# pure_midi.net
KiCad netlist of a schematic drawn in EAGLE
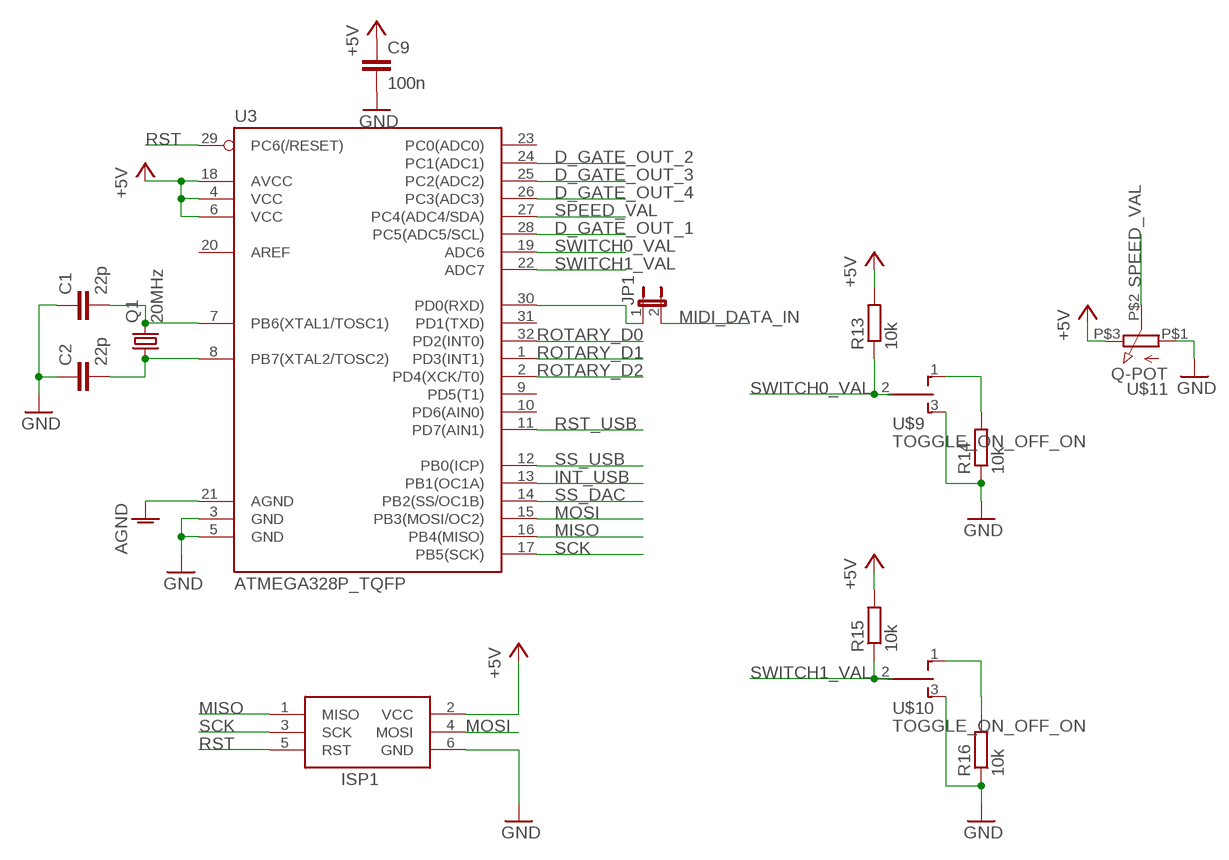
[diagram p0: schematic, sheet 1]
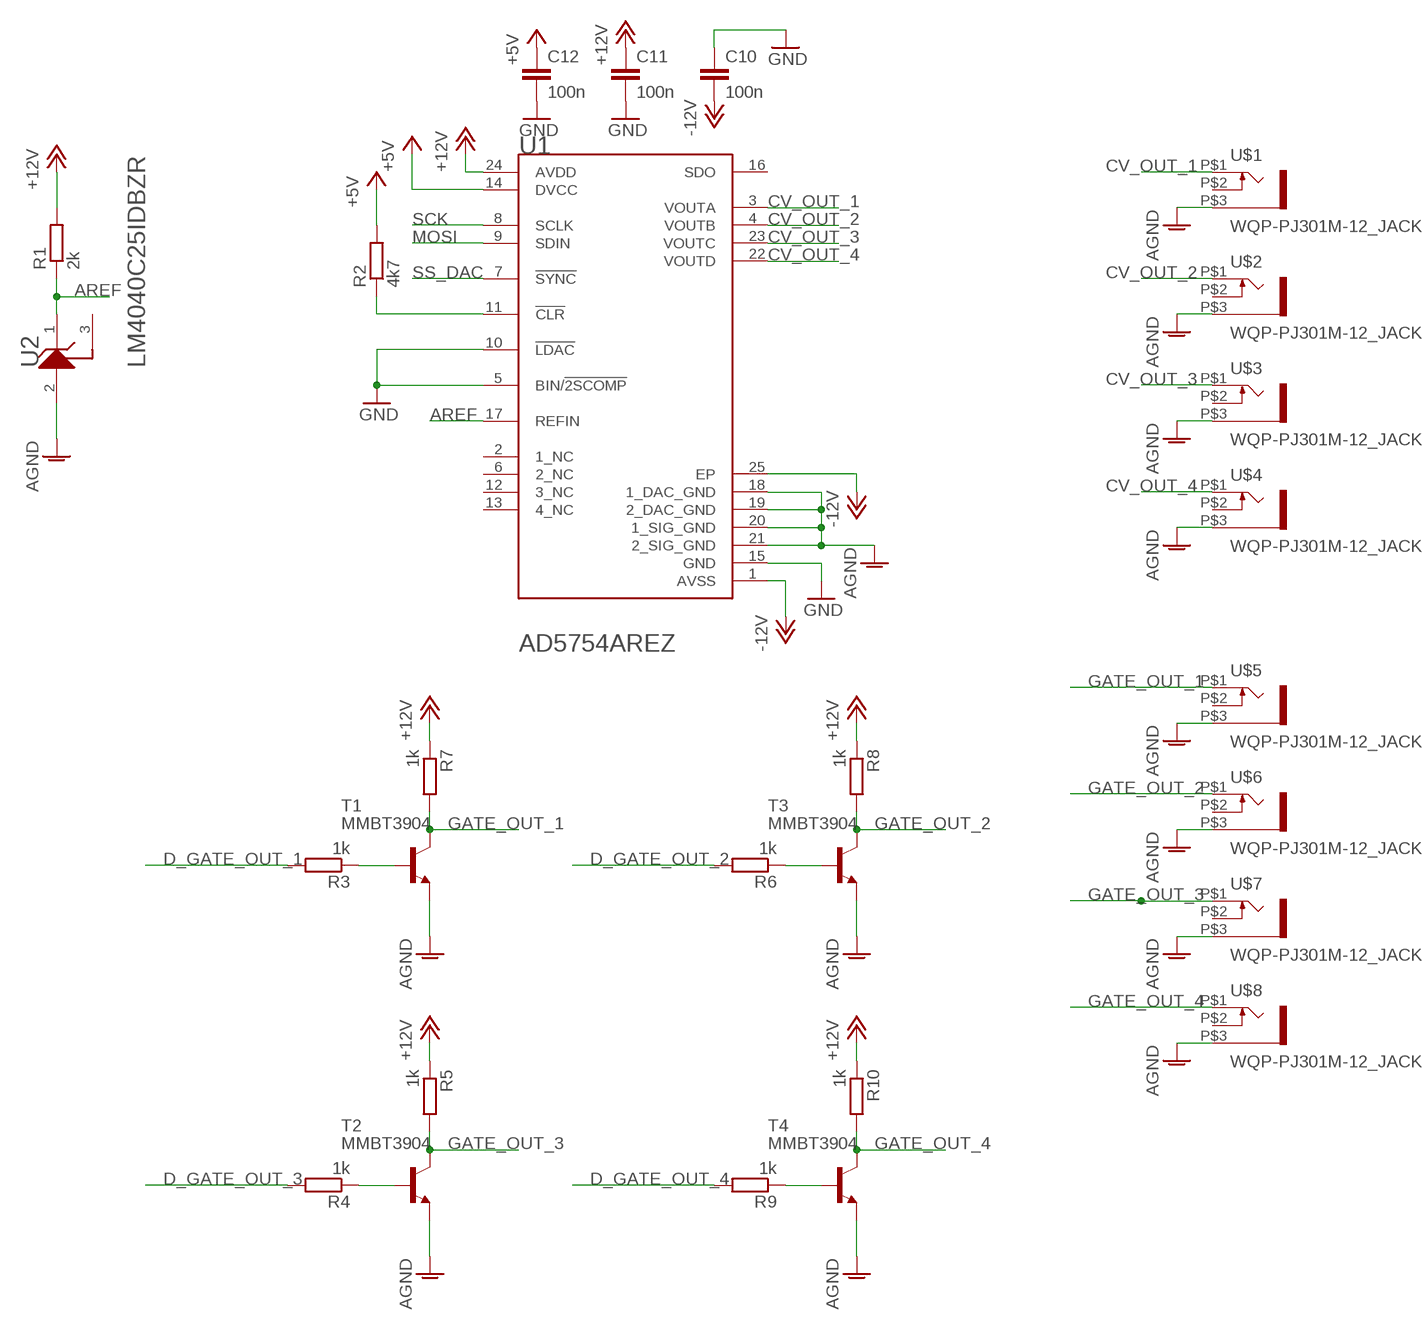
[diagram p1: schematic, sheet 2]
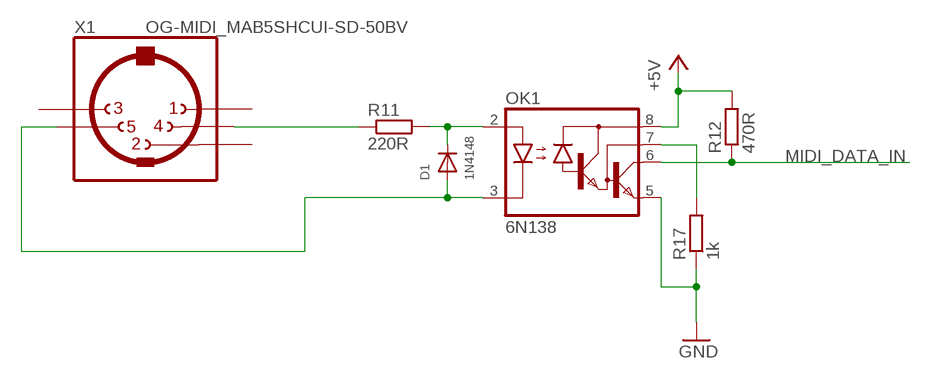
[diagram p2: schematic, sheet 3]
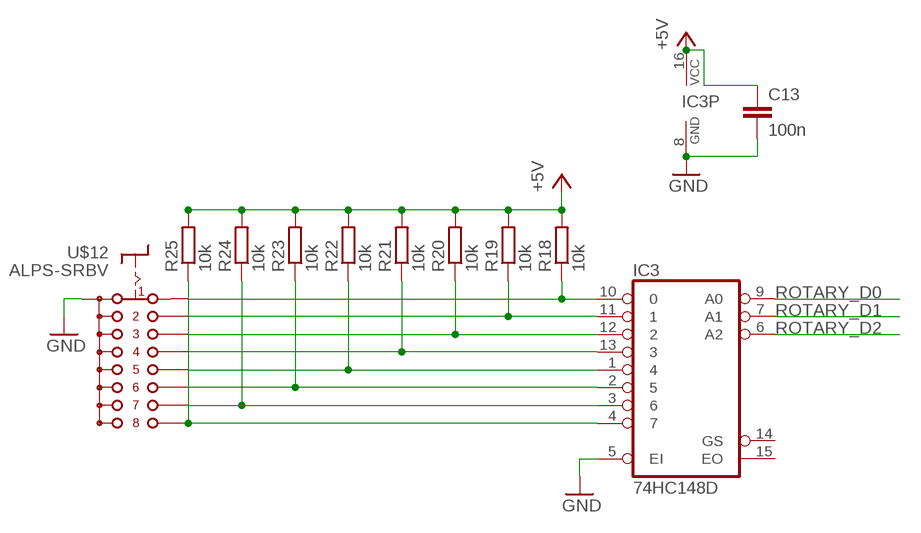
[diagram p3: schematic, sheet 4]
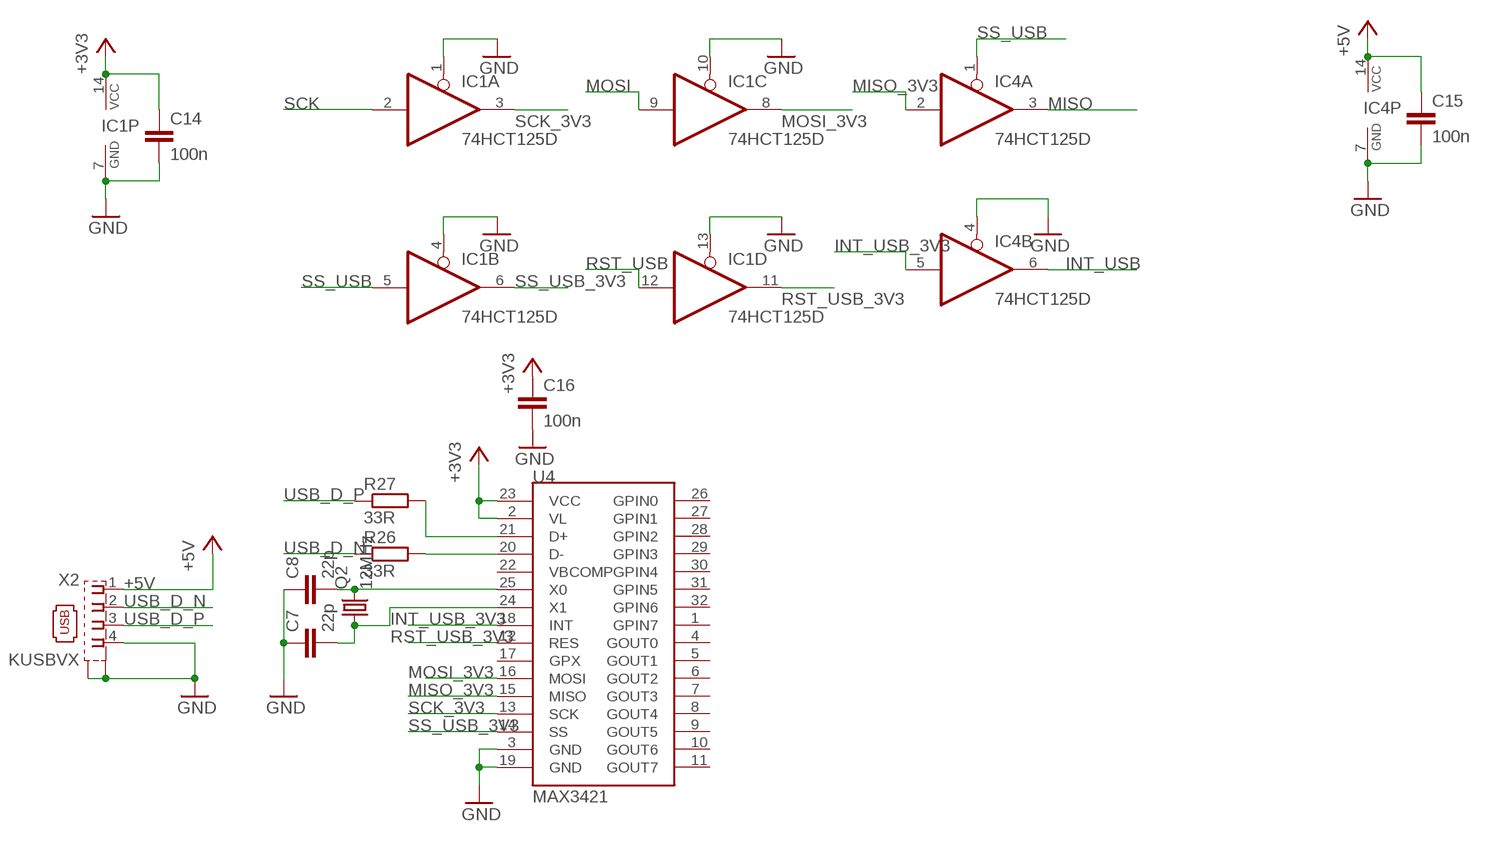
[diagram p4: schematic, sheet 5]
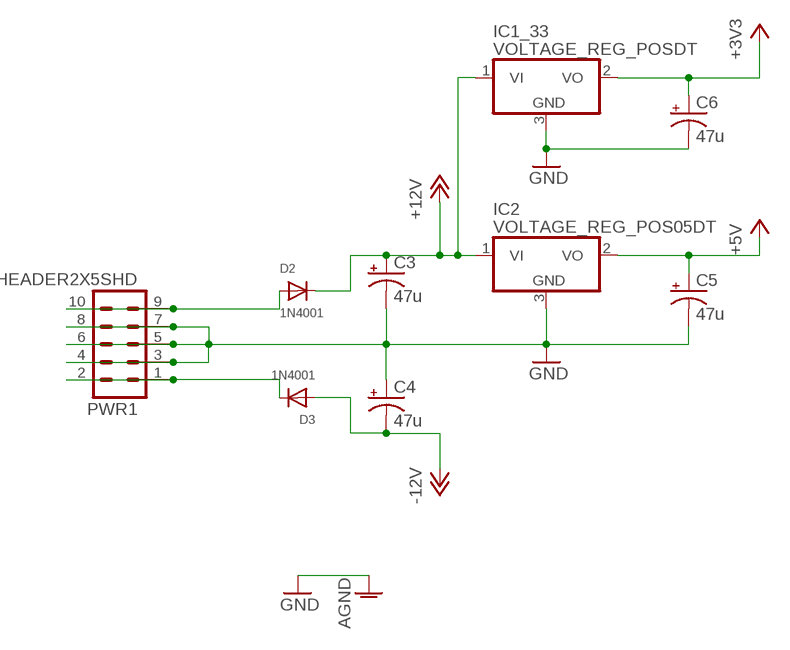
[diagram p5: schematic, sheet 6]

(export (version "E")
  (design (tool "Eeschema 10.0.6"))
  (components
    (comp (ref "C10")
      (value "100n")
      (footprint "eagle-import:C0805")
      (libsource (lib "eagle-import") (part "C-EUC0805"))
    )
    (comp (ref "C11")
      (value "100n")
      (footprint "eagle-import:C0805")
      (libsource (lib "eagle-import") (part "C-EUC0805"))
    )
    (comp (ref "C12")
      (value "100n")
      (footprint "eagle-import:C0805")
      (libsource (lib "eagle-import") (part "C-EUC0805"))
    )
    (comp (ref "R1")
      (value "2k")
      (footprint "eagle-import:R0805")
      (libsource (lib "eagle-import") (part "R-EU_R0805"))
    )
    (comp (ref "R2")
      (value "4k7")
      (footprint "eagle-import:R0805")
      (libsource (lib "eagle-import") (part "R-EU_R0805"))
    )
    (comp (ref "R3")
      (value "1k")
      (footprint "eagle-import:R0805")
      (libsource (lib "eagle-import") (part "R-EU_R0805"))
    )
    (comp (ref "R4")
      (value "1k")
      (footprint "eagle-import:R0805")
      (libsource (lib "eagle-import") (part "R-EU_R0805"))
    )
    (comp (ref "R5")
      (value "1k")
      (footprint "eagle-import:R0805")
      (libsource (lib "eagle-import") (part "R-EU_R0805"))
    )
    (comp (ref "R6")
      (value "1k")
      (footprint "eagle-import:R0805")
      (libsource (lib "eagle-import") (part "R-EU_R0805"))
    )
    (comp (ref "R7")
      (value "1k")
      (footprint "eagle-import:R0805")
      (libsource (lib "eagle-import") (part "R-EU_R0805"))
    )
    (comp (ref "R8")
      (value "1k")
      (footprint "eagle-import:R0805")
      (libsource (lib "eagle-import") (part "R-EU_R0805"))
    )
    (comp (ref "R9")
      (value "1k")
      (footprint "eagle-import:R0805")
      (libsource (lib "eagle-import") (part "R-EU_R0805"))
    )
    (comp (ref "R10")
      (value "1k")
      (footprint "eagle-import:R0805")
      (libsource (lib "eagle-import") (part "R-EU_R0805"))
    )
    (comp (ref "T1")
      (value "MMBT3904")
      (footprint "eagle-import:SOT23-EBC")
      (libsource (lib "eagle-import") (part "-NPN-SOT23-EBC"))
    )
    (comp (ref "T2")
      (value "MMBT3904")
      (footprint "eagle-import:SOT23-EBC")
      (libsource (lib "eagle-import") (part "-NPN-SOT23-EBC"))
    )
    (comp (ref "T3")
      (value "MMBT3904")
      (footprint "eagle-import:SOT23-EBC")
      (libsource (lib "eagle-import") (part "-NPN-SOT23-EBC"))
    )
    (comp (ref "T4")
      (value "MMBT3904")
      (footprint "eagle-import:SOT23-EBC")
      (libsource (lib "eagle-import") (part "-NPN-SOT23-EBC"))
    )
    (comp (ref "U$1")
      (value "WQP-PJ301M-12_JACK")
      (footprint "eagle-import:WQP-PJ301M-12_JACK")
      (libsource (lib "eagle-import") (part "WQP-PJ301M-12_JACK"))
    )
    (comp (ref "U$2")
      (value "WQP-PJ301M-12_JACK")
      (footprint "eagle-import:WQP-PJ301M-12_JACK")
      (libsource (lib "eagle-import") (part "WQP-PJ301M-12_JACK"))
    )
    (comp (ref "U$3")
      (value "WQP-PJ301M-12_JACK")
      (footprint "eagle-import:WQP-PJ301M-12_JACK")
      (libsource (lib "eagle-import") (part "WQP-PJ301M-12_JACK"))
    )
    (comp (ref "U$4")
      (value "WQP-PJ301M-12_JACK")
      (footprint "eagle-import:WQP-PJ301M-12_JACK")
      (libsource (lib "eagle-import") (part "WQP-PJ301M-12_JACK"))
    )
    (comp (ref "U$5")
      (value "WQP-PJ301M-12_JACK")
      (footprint "eagle-import:WQP-PJ301M-12_JACK")
      (libsource (lib "eagle-import") (part "WQP-PJ301M-12_JACK"))
    )
    (comp (ref "U$6")
      (value "WQP-PJ301M-12_JACK")
      (footprint "eagle-import:WQP-PJ301M-12_JACK")
      (libsource (lib "eagle-import") (part "WQP-PJ301M-12_JACK"))
    )
    (comp (ref "U$7")
      (value "WQP-PJ301M-12_JACK")
      (footprint "eagle-import:WQP-PJ301M-12_JACK")
      (libsource (lib "eagle-import") (part "WQP-PJ301M-12_JACK"))
    )
    (comp (ref "U$8")
      (value "WQP-PJ301M-12_JACK")
      (footprint "eagle-import:WQP-PJ301M-12_JACK")
      (libsource (lib "eagle-import") (part "WQP-PJ301M-12_JACK"))
    )
    (comp (ref "U1")
      (value "ANALOG_DEVICES_INC_AD5754AREZANALOG_DEVICES_INC_AD5754AREZ_0_0")
      (footprint "eagle-import:ANALOG_DEVICES_INC_AD5754AREZ_0")
      (fields
        (field (name "DIGIKEY_PART_NUMBER") "AD5754AREZ-ND")
        (field (name "MF") "Analog Devices Inc")
        (field (name "MOUSER_PART_NUMBER") "584-AD5754AREZ")
      )
      (libsource (lib "eagle-import") (part "ANALOG_DEVICES_INC_AD5754AREZANALOG_DEVICES_INC_AD5754AREZ_0_0"))
    )
    (comp (ref "U2")
      (value "TEXAS_INSTRUMENTS_LM4040C25IDBZRTEXAS_INSTRUMENTS_LM4040C25IDBZR_0_1")
      (footprint "eagle-import:TEXAS_INSTRUMENTS_LM4040C25IDBZR_1")
      (fields (field (name "MF") "Texas Instruments") (field (name "MPN") "LM4040C25IDBZR"))
      (libsource (lib "eagle-import") (part "TEXAS_INSTRUMENTS_LM4040C25IDBZRTEXAS_INSTRUMENTS_LM4040C25IDBZR_0_1"))
    )
    (comp (ref "C3")
      (value "47u")
      (footprint "eagle-import:153CLV-0505")
      (libsource (lib "eagle-import") (part "CAPACITOR_POL-US153CLV-0505"))
    )
    (comp (ref "C4")
      (value "47u")
      (footprint "eagle-import:153CLV-0505")
      (libsource (lib "eagle-import") (part "CAPACITOR_POL-US153CLV-0505"))
    )
    (comp (ref "C5")
      (value "47u")
      (footprint "eagle-import:153CLV-0505")
      (libsource (lib "eagle-import") (part "CAPACITOR_POL-US153CLV-0505"))
    )
    (comp (ref "C6")
      (value "47u")
      (footprint "eagle-import:153CLV-0505")
      (libsource (lib "eagle-import") (part "CAPACITOR_POL-US153CLV-0505"))
    )
    (comp (ref "D2")
      (value "1N4001")
      (footprint "eagle-import:SMADIODE")
      (libsource (lib "eagle-import") (part "DIODESMA"))
    )
    (comp (ref "D3")
      (value "1N4001")
      (footprint "eagle-import:SMADIODE")
      (libsource (lib "eagle-import") (part "DIODESMA"))
    )
    (comp (ref "IC1_33")
      (value "VOLTAGE_REG_POSDT")
      (footprint "eagle-import:TO252")
      (libsource (lib "eagle-import") (part "VOLTAGE_REG_POSDT"))
    )
    (comp (ref "IC2")
      (value "VOLTAGE_REG_POS05DT")
      (footprint "eagle-import:TO252")
      (libsource (lib "eagle-import") (part "VOLTAGE_REG_POSDT05"))
    )
    (comp (ref "PWR1")
      (value "HEADER2X5SHD")
      (footprint "eagle-import:2X5-SHROUDED")
      (libsource (lib "eagle-import") (part "HEADER2X5SHD"))
    )
    (comp (ref "C7")
      (value "22p")
      (footprint "eagle-import:C0805")
      (libsource (lib "eagle-import") (part "C-EUC0805"))
    )
    (comp (ref "C8")
      (value "22p")
      (footprint "eagle-import:C0805")
      (libsource (lib "eagle-import") (part "C-EUC0805"))
    )
    (comp (ref "C14")
      (value "100n")
      (footprint "eagle-import:C0805")
      (libsource (lib "eagle-import") (part "C-EUC0805"))
    )
    (comp (ref "C15")
      (value "100n")
      (footprint "eagle-import:C0805")
      (libsource (lib "eagle-import") (part "C-EUC0805"))
    )
    (comp (ref "C16")
      (value "100n")
      (footprint "eagle-import:C0805")
      (libsource (lib "eagle-import") (part "C-EUC0805"))
    )
    (comp (ref "IC1")
      (value "74HCT125D")
      (footprint "eagle-import:SO14")
      (libsource (lib "eagle-import") (part "74125DHCT"))
    )
    (comp (ref "IC4")
      (value "74HCT125D")
      (footprint "eagle-import:SO14")
      (libsource (lib "eagle-import") (part "74125DHCT"))
    )
    (comp (ref "Q2")
      (value "12MHz")
      (footprint "eagle-import:HC49UP")
      (libsource (lib "eagle-import") (part "CRYSTALHC49UP"))
    )
    (comp (ref "R26")
      (value "33R")
      (footprint "eagle-import:R0805")
      (libsource (lib "eagle-import") (part "R-EU_R0805"))
    )
    (comp (ref "R27")
      (value "33R")
      (footprint "eagle-import:R0805")
      (libsource (lib "eagle-import") (part "R-EU_R0805"))
    )
    (comp (ref "U4")
      (value "MAX3421")
      (footprint "eagle-import:TQFP32-5MM")
      (libsource (lib "eagle-import") (part "MAX3421ESMD"))
    )
    (comp (ref "X2")
      (value "KUSBVX")
      (footprint "eagle-import:KUSBVX")
      (libsource (lib "eagle-import") (part "KUSBVX"))
    )
    (comp (ref "C1")
      (value "22p")
      (footprint "eagle-import:C0805")
      (libsource (lib "eagle-import") (part "C-EUC0805"))
    )
    (comp (ref "C2")
      (value "22p")
      (footprint "eagle-import:C0805")
      (libsource (lib "eagle-import") (part "C-EUC0805"))
    )
    (comp (ref "C9")
      (value "100n")
      (footprint "eagle-import:C0805")
      (libsource (lib "eagle-import") (part "C-EUC0805"))
    )
    (comp (ref "ISP1")
      (value "AVRISP-6")
      (footprint "eagle-import:AVRISP")
      (libsource (lib "eagle-import") (part "AVRISP-6"))
    )
    (comp (ref "JP1")
      (value "JP1E")
      (footprint "eagle-import:JP1")
      (libsource (lib "eagle-import") (part "JP1E"))
    )
    (comp (ref "Q1")
      (value "20MHz")
      (footprint "eagle-import:HC49UP")
      (libsource (lib "eagle-import") (part "CRYSTALHC49UP"))
    )
    (comp (ref "R13")
      (value "10k")
      (footprint "eagle-import:R0805")
      (libsource (lib "eagle-import") (part "resistor_348_R-EU_R0805"))
    )
    (comp (ref "R14")
      (value "10k")
      (footprint "eagle-import:R0805")
      (libsource (lib "eagle-import") (part "resistor_348_R-EU_R0805"))
    )
    (comp (ref "R15")
      (value "10k")
      (footprint "eagle-import:R0805")
      (libsource (lib "eagle-import") (part "resistor_348_R-EU_R0805"))
    )
    (comp (ref "R16")
      (value "10k")
      (footprint "eagle-import:R0805")
      (libsource (lib "eagle-import") (part "resistor_348_R-EU_R0805"))
    )
    (comp (ref "U$9")
      (value "TOGGLE_ON_OFF_ON")
      (footprint "eagle-import:TOGGLE_ON_OFF_ON")
      (libsource (lib "eagle-import") (part "TOGGLE_ON_OFF_ON"))
    )
    (comp (ref "U$10")
      (value "TOGGLE_ON_OFF_ON")
      (footprint "eagle-import:TOGGLE_ON_OFF_ON")
      (libsource (lib "eagle-import") (part "TOGGLE_ON_OFF_ON"))
    )
    (comp (ref "U$11")
      (value "Q-POT")
      (footprint "eagle-import:Q-POT")
      (libsource (lib "eagle-import") (part "Q-POT"))
    )
    (comp (ref "U3")
      (value "ATMEGA328P_TQFP")
      (footprint "eagle-import:TQFP32-08")
      (libsource (lib "eagle-import") (part "ATMEGA328P_TQFP"))
    )
    (comp (ref "C13")
      (value "100n")
      (footprint "eagle-import:C0805")
      (libsource (lib "eagle-import") (part "C-EUC0805"))
    )
    (comp (ref "IC3")
      (value "74HC148D")
      (footprint "eagle-import:SO16")
      (libsource (lib "eagle-import") (part "74148DHC"))
    )
    (comp (ref "R18")
      (value "10k")
      (footprint "eagle-import:R0805")
      (libsource (lib "eagle-import") (part "R-EU_R0805"))
    )
    (comp (ref "R19")
      (value "10k")
      (footprint "eagle-import:R0805")
      (libsource (lib "eagle-import") (part "R-EU_R0805"))
    )
    (comp (ref "R20")
      (value "10k")
      (footprint "eagle-import:R0805")
      (libsource (lib "eagle-import") (part "R-EU_R0805"))
    )
    (comp (ref "R21")
      (value "10k")
      (footprint "eagle-import:R0805")
      (libsource (lib "eagle-import") (part "R-EU_R0805"))
    )
    (comp (ref "R22")
      (value "10k")
      (footprint "eagle-import:R0805")
      (libsource (lib "eagle-import") (part "R-EU_R0805"))
    )
    (comp (ref "R23")
      (value "10k")
      (footprint "eagle-import:R0805")
      (libsource (lib "eagle-import") (part "R-EU_R0805"))
    )
    (comp (ref "R24")
      (value "10k")
      (footprint "eagle-import:R0805")
      (libsource (lib "eagle-import") (part "R-EU_R0805"))
    )
    (comp (ref "R25")
      (value "10k")
      (footprint "eagle-import:R0805")
      (libsource (lib "eagle-import") (part "R-EU_R0805"))
    )
    (comp (ref "U$12")
      (value "ALPS-SRBV")
      (footprint "eagle-import:ALPS-SRBV")
      (libsource (lib "eagle-import") (part "ALPS-SRBV"))
    )
    (comp (ref "D1")
      (value "1N4148")
      (footprint "eagle-import:SOD-323F")
      (libsource (lib "eagle-import") (part "adafruit_420_DIODESOD-323F"))
    )
    (comp (ref "OK1")
      (value "6N138")
      (footprint "eagle-import:DIL08")
      (fields (field (name "MF") "VISHAY/TELEFUNKEN"))
      (libsource (lib "eagle-import") (part "6N138"))
    )
    (comp (ref "R11")
      (value "220R")
      (footprint "eagle-import:R0805")
      (libsource (lib "eagle-import") (part "resistor_348_R-EU_R0805"))
    )
    (comp (ref "R12")
      (value "470R")
      (footprint "eagle-import:R0805")
      (libsource (lib "eagle-import") (part "resistor_348_R-EU_R0805"))
    )
    (comp (ref "R17")
      (value "1k")
      (footprint "eagle-import:R0805")
      (libsource (lib "eagle-import") (part "resistor_348_R-EU_R0805"))
    )
    (comp (ref "X1")
      (value "OG-MIDI_MAB5SHCUI-SD-50BV")
      (footprint "eagle-import:OG-MIDI_SD-50BV")
      (libsource (lib "eagle-import") (part "OG-MIDI_MAB5SHCUI-SD-50BV"))
    )
  )
  (nets
    (net (code "1") (name "+3V3") (class "Default")
      (node (ref "C14") (pin "1") (pinfunction "1_1") (pintype "passive"))
      (node (ref "C16") (pin "1") (pinfunction "1_1") (pintype "passive"))
      (node (ref "C6") (pin "+") (pinfunction "+_+") (pintype "passive"))
      (node (ref "IC1") (pin "14") (pinfunction "VCC_14") (pintype "power_in"))
      (node (ref "IC1_33") (pin "2") (pinfunction "VO_2") (pintype "passive"))
      (node (ref "U4") (pin "2") (pinfunction "VL_2") (pintype "bidirectional"))
      (node (ref "U4") (pin "23") (pinfunction "VCC_23") (pintype "bidirectional"))
    )
    (net (code "2") (name "+5V") (class "Default")
      (node (ref "C12") (pin "1") (pinfunction "1_1") (pintype "passive"))
      (node (ref "C13") (pin "1") (pinfunction "1_1") (pintype "passive"))
      (node (ref "C15") (pin "1") (pinfunction "1_1") (pintype "passive"))
      (node (ref "C5") (pin "+") (pinfunction "+_+") (pintype "passive"))
      (node (ref "C9") (pin "1") (pinfunction "1_1") (pintype "passive"))
      (node (ref "IC2") (pin "2") (pinfunction "VO_2") (pintype "passive"))
      (node (ref "IC3") (pin "16") (pinfunction "VCC_16") (pintype "power_in"))
      (node (ref "IC4") (pin "14") (pinfunction "VCC_14") (pintype "power_in"))
      (node (ref "ISP1") (pin "2") (pinfunction "VCC_2") (pintype "power_in"))
      (node (ref "OK1") (pin "8") (pinfunction "VCC_8") (pintype "passive"))
      (node (ref "R12") (pin "2") (pinfunction "2_2") (pintype "passive"))
      (node (ref "R13") (pin "2") (pinfunction "2_2") (pintype "passive"))
      (node (ref "R15") (pin "2") (pinfunction "2_2") (pintype "passive"))
      (node (ref "R18") (pin "2") (pinfunction "2_2") (pintype "passive"))
      (node (ref "R19") (pin "2") (pinfunction "2_2") (pintype "passive"))
      (node (ref "R2") (pin "2") (pinfunction "2_2") (pintype "passive"))
      (node (ref "R20") (pin "2") (pinfunction "2_2") (pintype "passive"))
      (node (ref "R21") (pin "2") (pinfunction "2_2") (pintype "passive"))
      (node (ref "R22") (pin "2") (pinfunction "2_2") (pintype "passive"))
      (node (ref "R23") (pin "2") (pinfunction "2_2") (pintype "passive"))
      (node (ref "R24") (pin "2") (pinfunction "2_2") (pintype "passive"))
      (node (ref "R25") (pin "2") (pinfunction "2_2") (pintype "passive"))
      (node (ref "U$11") (pin "P$3") (pinfunction "3_P$3") (pintype "passive"))
      (node (ref "U1") (pin "14") (pinfunction "DVCC_14") (pintype "power_in"))
      (node (ref "U3") (pin "18") (pinfunction "AVCC_18") (pintype "bidirectional"))
      (node (ref "U3") (pin "4") (pinfunction "VCC_4") (pintype "bidirectional"))
      (node (ref "U3") (pin "6") (pinfunction "VCC_6") (pintype "bidirectional"))
      (node (ref "X2") (pin "1") (pinfunction "1_1") (pintype "passive"))
    )
    (net (code "3") (name "+12V") (class "Default")
      (node (ref "C11") (pin "1") (pinfunction "1_1") (pintype "passive"))
      (node (ref "C3") (pin "+") (pinfunction "+_+") (pintype "passive"))
      (node (ref "D2") (pin "C") (pinfunction "C_C") (pintype "passive"))
      (node (ref "IC1_33") (pin "1") (pinfunction "VI_1") (pintype "input"))
      (node (ref "IC2") (pin "1") (pinfunction "VI_1") (pintype "input"))
      (node (ref "R1") (pin "2") (pinfunction "2_2") (pintype "passive"))
      (node (ref "R10") (pin "1") (pinfunction "1_1") (pintype "passive"))
      (node (ref "R5") (pin "1") (pinfunction "1_1") (pintype "passive"))
      (node (ref "R7") (pin "1") (pinfunction "1_1") (pintype "passive"))
      (node (ref "R8") (pin "1") (pinfunction "1_1") (pintype "passive"))
      (node (ref "U1") (pin "24") (pinfunction "AVDD_24") (pintype "power_in"))
    )
    (net (code "4") (name "-12V") (class "Default")
      (node (ref "C10") (pin "2") (pinfunction "2_2") (pintype "passive"))
      (node (ref "C4") (pin "-") (pinfunction "-_-") (pintype "passive"))
      (node (ref "D3") (pin "A") (pinfunction "A_A") (pintype "passive"))
      (node (ref "U1") (pin "1") (pinfunction "AVSS_1") (pintype "power_in"))
      (node (ref "U1") (pin "25") (pinfunction "EP_25") (pintype "power_in"))
    )
    (net (code "5") (name "AGND") (class "Default")
      (node (ref "C1") (pin "1") (pinfunction "1_1") (pintype "passive"))
      (node (ref "C10") (pin "1") (pinfunction "1_1") (pintype "passive"))
      (node (ref "C11") (pin "2") (pinfunction "2_2") (pintype "passive"))
      (node (ref "C12") (pin "2") (pinfunction "2_2") (pintype "passive"))
      (node (ref "C13") (pin "2") (pinfunction "2_2") (pintype "passive"))
      (node (ref "C14") (pin "2") (pinfunction "2_2") (pintype "passive"))
      (node (ref "C15") (pin "2") (pinfunction "2_2") (pintype "passive"))
      (node (ref "C16") (pin "2") (pinfunction "2_2") (pintype "passive"))
      (node (ref "C2") (pin "1") (pinfunction "1_1") (pintype "passive"))
      (node (ref "C3") (pin "-") (pinfunction "-_-") (pintype "passive"))
      (node (ref "C4") (pin "+") (pinfunction "+_+") (pintype "passive"))
      (node (ref "C5") (pin "-") (pinfunction "-_-") (pintype "passive"))
      (node (ref "C6") (pin "-") (pinfunction "-_-") (pintype "passive"))
      (node (ref "C7") (pin "1") (pinfunction "1_1") (pintype "passive"))
      (node (ref "C8") (pin "1") (pinfunction "1_1") (pintype "passive"))
      (node (ref "C9") (pin "2") (pinfunction "2_2") (pintype "passive"))
      (node (ref "IC1") (pin "1") (pinfunction "OE_1") (pintype "input"))
      (node (ref "IC1") (pin "10") (pinfunction "OE_10") (pintype "input"))
      (node (ref "IC1") (pin "13") (pinfunction "OE_13") (pintype "input"))
      (node (ref "IC1") (pin "4") (pinfunction "OE_4") (pintype "input"))
      (node (ref "IC1") (pin "7") (pinfunction "GND_7") (pintype "power_in"))
      (node (ref "IC1_33") (pin "3") (pinfunction "GND_3") (pintype "passive"))
      (node (ref "IC2") (pin "3") (pinfunction "GND_3") (pintype "passive"))
      (node (ref "IC3") (pin "5") (pinfunction "EI_5") (pintype "input"))
      (node (ref "IC3") (pin "8") (pinfunction "GND_8") (pintype "power_in"))
      (node (ref "IC4") (pin "4") (pinfunction "OE_4") (pintype "input"))
      (node (ref "IC4") (pin "7") (pinfunction "GND_7") (pintype "power_in"))
      (node (ref "ISP1") (pin "6") (pinfunction "GND_6") (pintype "power_in"))
      (node (ref "OK1") (pin "5") (pinfunction "GND_5") (pintype "passive"))
      (node (ref "PWR1") (pin "3") (pinfunction "3_3") (pintype "passive"))
      (node (ref "PWR1") (pin "4") (pinfunction "4_4") (pintype "passive"))
      (node (ref "PWR1") (pin "5") (pinfunction "5_5") (pintype "passive"))
      (node (ref "PWR1") (pin "6") (pinfunction "6_6") (pintype "passive"))
      (node (ref "PWR1") (pin "7") (pinfunction "7_7") (pintype "passive"))
      (node (ref "PWR1") (pin "8") (pinfunction "8_8") (pintype "passive"))
      (node (ref "R14") (pin "1") (pinfunction "1_1") (pintype "passive"))
      (node (ref "R16") (pin "1") (pinfunction "1_1") (pintype "passive"))
      (node (ref "R17") (pin "1") (pinfunction "1_1") (pintype "passive"))
      (node (ref "T1") (pin "E") (pinfunction "E_E") (pintype "passive"))
      (node (ref "T2") (pin "E") (pinfunction "E_E") (pintype "passive"))
      (node (ref "T3") (pin "E") (pinfunction "E_E") (pintype "passive"))
      (node (ref "T4") (pin "E") (pinfunction "E_E") (pintype "passive"))
      (node (ref "U$1") (pin "P$3") (pinfunction "1_P$3") (pintype "passive"))
      (node (ref "U$10") (pin "3") (pinfunction "S_3") (pintype "passive"))
      (node (ref "U$11") (pin "P$1") (pinfunction "1_P$1") (pintype "passive"))
      (node (ref "U$12") (pin "COM") (pinfunction "A_COM") (pintype "passive"))
      (node (ref "U$12") (pin "COM2") (pinfunction "A_COM2") (pintype "passive"))
      (node (ref "U$2") (pin "P$3") (pinfunction "1_P$3") (pintype "passive"))
      (node (ref "U$3") (pin "P$3") (pinfunction "1_P$3") (pintype "passive"))
      (node (ref "U$4") (pin "P$3") (pinfunction "1_P$3") (pintype "passive"))
      (node (ref "U$5") (pin "P$3") (pinfunction "1_P$3") (pintype "passive"))
      (node (ref "U$6") (pin "P$3") (pinfunction "1_P$3") (pintype "passive"))
      (node (ref "U$7") (pin "P$3") (pinfunction "1_P$3") (pintype "passive"))
      (node (ref "U$8") (pin "P$3") (pinfunction "1_P$3") (pintype "passive"))
      (node (ref "U$9") (pin "3") (pinfunction "S_3") (pintype "passive"))
      (node (ref "U1") (pin "10") (pinfunction "~{LDAC}_10") (pintype "input"))
      (node (ref "U1") (pin "15") (pinfunction "GND_15") (pintype "power_in"))
      (node (ref "U1") (pin "18") (pinfunction "1_DAC_GND_18") (pintype "power_in"))
      (node (ref "U1") (pin "19") (pinfunction "2_DAC_GND_19") (pintype "power_in"))
      (node (ref "U1") (pin "20") (pinfunction "1_SIG_GND_20") (pintype "power_in"))
      (node (ref "U1") (pin "21") (pinfunction "2_SIG_GND_21") (pintype "power_in"))
      (node (ref "U1") (pin "5") (pinfunction "BIN/~{2SCOMP}_5") (pintype "input"))
      (node (ref "U2") (pin "2") (pinfunction "ANODE_2") (pintype "passive"))
      (node (ref "U3") (pin "21") (pinfunction "AGND_21") (pintype "bidirectional"))
      (node (ref "U3") (pin "3") (pinfunction "GND_3") (pintype "bidirectional"))
      (node (ref "U3") (pin "5") (pinfunction "GND_5") (pintype "bidirectional"))
      (node (ref "U4") (pin "19") (pinfunction "GND_19") (pintype "bidirectional"))
      (node (ref "U4") (pin "3") (pinfunction "GND_3") (pintype "bidirectional"))
      (node (ref "X2") (pin "4") (pinfunction "4_4") (pintype "passive"))
      (node (ref "X2") (pin "M1") (pinfunction "S1_M1") (pintype "passive"))
      (node (ref "X2") (pin "M2") (pinfunction "S2_M2") (pintype "passive"))
    )
    (net (code "6") (name "AREF") (class "Default")
      (node (ref "R1") (pin "1") (pinfunction "1_1") (pintype "passive"))
      (node (ref "U1") (pin "17") (pinfunction "REFIN_17") (pintype "input"))
      (node (ref "U2") (pin "1") (pinfunction "CATHODE_1") (pintype "passive"))
    )
    (net (code "7") (name "CV_OUT_1") (class "Default")
      (node (ref "U$1") (pin "P$1") (pinfunction "2_P$1") (pintype "passive"))
      (node (ref "U1") (pin "3") (pinfunction "VOUTA_3") (pintype "output"))
    )
    (net (code "8") (name "CV_OUT_2") (class "Default")
      (node (ref "U$2") (pin "P$1") (pinfunction "2_P$1") (pintype "passive"))
      (node (ref "U1") (pin "4") (pinfunction "VOUTB_4") (pintype "output"))
    )
    (net (code "9") (name "CV_OUT_3") (class "Default")
      (node (ref "U$3") (pin "P$1") (pinfunction "2_P$1") (pintype "passive"))
      (node (ref "U1") (pin "23") (pinfunction "VOUTC_23") (pintype "output"))
    )
    (net (code "10") (name "CV_OUT_4") (class "Default")
      (node (ref "U$4") (pin "P$1") (pinfunction "2_P$1") (pintype "passive"))
      (node (ref "U1") (pin "22") (pinfunction "VOUTD_22") (pintype "output"))
    )
    (net (code "11") (name "D_GATE_OUT_1") (class "Default")
      (node (ref "R3") (pin "2") (pinfunction "2_2") (pintype "passive"))
      (node (ref "U3") (pin "28") (pinfunction "PC5(ADC5/SCL)_28") (pintype "bidirectional"))
    )
    (net (code "12") (name "D_GATE_OUT_2") (class "Default")
      (node (ref "R6") (pin "2") (pinfunction "2_2") (pintype "passive"))
      (node (ref "U3") (pin "24") (pinfunction "PC1(ADC1)_24") (pintype "bidirectional"))
    )
    (net (code "13") (name "D_GATE_OUT_3") (class "Default")
      (node (ref "R4") (pin "2") (pinfunction "2_2") (pintype "passive"))
      (node (ref "U3") (pin "25") (pinfunction "PC2(ADC2)_25") (pintype "bidirectional"))
    )
    (net (code "14") (name "D_GATE_OUT_4") (class "Default")
      (node (ref "R9") (pin "2") (pinfunction "2_2") (pintype "passive"))
      (node (ref "U3") (pin "26") (pinfunction "PC3(ADC3)_26") (pintype "bidirectional"))
    )
    (net (code "15") (name "GATE_OUT_1") (class "Default")
      (node (ref "R7") (pin "2") (pinfunction "2_2") (pintype "passive"))
      (node (ref "T1") (pin "C") (pinfunction "C_C") (pintype "passive"))
      (node (ref "U$5") (pin "P$1") (pinfunction "2_P$1") (pintype "passive"))
    )
    (net (code "16") (name "GATE_OUT_2") (class "Default")
      (node (ref "R8") (pin "2") (pinfunction "2_2") (pintype "passive"))
      (node (ref "T3") (pin "C") (pinfunction "C_C") (pintype "passive"))
      (node (ref "U$6") (pin "P$1") (pinfunction "2_P$1") (pintype "passive"))
    )
    (net (code "17") (name "GATE_OUT_3") (class "Default")
      (node (ref "R5") (pin "2") (pinfunction "2_2") (pintype "passive"))
      (node (ref "T2") (pin "C") (pinfunction "C_C") (pintype "passive"))
      (node (ref "U$7") (pin "P$1") (pinfunction "2_P$1") (pintype "passive"))
    )
    (net (code "18") (name "GATE_OUT_4") (class "Default")
      (node (ref "R10") (pin "2") (pinfunction "2_2") (pintype "passive"))
      (node (ref "T4") (pin "C") (pinfunction "C_C") (pintype "passive"))
      (node (ref "U$8") (pin "P$1") (pinfunction "2_P$1") (pintype "passive"))
    )
    (net (code "19") (name "INT_USB") (class "Default")
      (node (ref "IC4") (pin "6") (pinfunction "O_6") (pintype "tri_state"))
      (node (ref "U3") (pin "13") (pinfunction "PB1(OC1A)_13") (pintype "bidirectional"))
    )
    (net (code "20") (name "INT_USB_3V3") (class "Default")
      (node (ref "IC4") (pin "5") (pinfunction "I_5") (pintype "input"))
      (node (ref "U4") (pin "18") (pinfunction "INT_18") (pintype "bidirectional"))
    )
    (net (code "21") (name "MIDI_DATA_IN") (class "Default")
      (node (ref "JP1") (pin "2") (pinfunction "2_2") (pintype "passive"))
      (node (ref "OK1") (pin "6") (pinfunction "VO_6") (pintype "passive"))
      (node (ref "R12") (pin "1") (pinfunction "1_1") (pintype "passive"))
    )
    (net (code "22") (name "MISO") (class "Default")
      (node (ref "IC4") (pin "3") (pinfunction "O_3") (pintype "tri_state"))
      (node (ref "ISP1") (pin "1") (pinfunction "MISO_1") (pintype "input"))
      (node (ref "U3") (pin "16") (pinfunction "PB4(MISO)_16") (pintype "bidirectional"))
    )
    (net (code "23") (name "MISO_3V3") (class "Default")
      (node (ref "IC4") (pin "2") (pinfunction "I_2") (pintype "input"))
      (node (ref "U4") (pin "15") (pinfunction "MISO_15") (pintype "bidirectional"))
    )
    (net (code "24") (name "MOSI") (class "Default")
      (node (ref "IC1") (pin "9") (pinfunction "I_9") (pintype "input"))
      (node (ref "ISP1") (pin "4") (pinfunction "MOSI_4") (pintype "output"))
      (node (ref "U1") (pin "9") (pinfunction "SDIN_9") (pintype "input"))
      (node (ref "U3") (pin "15") (pinfunction "PB3(MOSI/OC2)_15") (pintype "bidirectional"))
    )
    (net (code "25") (name "MOSI_3V3") (class "Default")
      (node (ref "IC1") (pin "8") (pinfunction "O_8") (pintype "tri_state"))
      (node (ref "U4") (pin "16") (pinfunction "MOSI_16") (pintype "bidirectional"))
    )
    (net (code "26") (name "Net-(D2-PadA)") (class "Default")
      (node (ref "D2") (pin "A") (pinfunction "A_A") (pintype "passive"))
      (node (ref "PWR1") (pin "10") (pinfunction "10_10") (pintype "passive"))
      (node (ref "PWR1") (pin "9") (pinfunction "9_9") (pintype "passive"))
    )
    (net (code "27") (name "Net-(D3-PadC)") (class "Default")
      (node (ref "D3") (pin "C") (pinfunction "C_C") (pintype "passive"))
      (node (ref "PWR1") (pin "1") (pinfunction "1_1") (pintype "passive"))
      (node (ref "PWR1") (pin "2") (pinfunction "2_2") (pintype "passive"))
    )
    (net (code "28") (name "Net-(IC3A-0)") (class "Default")
      (node (ref "IC3") (pin "10") (pinfunction "0_10") (pintype "input"))
      (node (ref "R18") (pin "1") (pinfunction "1_1") (pintype "passive"))
      (node (ref "U$12") (pin "A") (pinfunction "1_A") (pintype "passive"))
    )
    (net (code "29") (name "Net-(IC3A-1)") (class "Default")
      (node (ref "IC3") (pin "11") (pinfunction "1_11") (pintype "input"))
      (node (ref "R19") (pin "1") (pinfunction "1_1") (pintype "passive"))
      (node (ref "U$12") (pin "B") (pinfunction "2_B") (pintype "passive"))
    )
    (net (code "30") (name "Net-(IC3A-2)") (class "Default")
      (node (ref "IC3") (pin "12") (pinfunction "2_12") (pintype "input"))
      (node (ref "R20") (pin "1") (pinfunction "1_1") (pintype "passive"))
      (node (ref "U$12") (pin "C") (pinfunction "3_C") (pintype "passive"))
    )
    (net (code "31") (name "Net-(IC3A-3)") (class "Default")
      (node (ref "IC3") (pin "13") (pinfunction "3_13") (pintype "input"))
      (node (ref "R21") (pin "1") (pinfunction "1_1") (pintype "passive"))
      (node (ref "U$12") (pin "D") (pinfunction "4_D") (pintype "passive"))
    )
    (net (code "32") (name "Net-(IC3A-4)") (class "Default")
      (node (ref "IC3") (pin "1") (pinfunction "4_1") (pintype "input"))
      (node (ref "R22") (pin "1") (pinfunction "1_1") (pintype "passive"))
      (node (ref "U$12") (pin "E") (pinfunction "5_E") (pintype "passive"))
    )
    (net (code "33") (name "Net-(IC3A-5)") (class "Default")
      (node (ref "IC3") (pin "2") (pinfunction "5_2") (pintype "input"))
      (node (ref "R23") (pin "1") (pinfunction "1_1") (pintype "passive"))
      (node (ref "U$12") (pin "F") (pinfunction "6_F") (pintype "passive"))
    )
    (net (code "34") (name "Net-(IC3A-6)") (class "Default")
      (node (ref "IC3") (pin "3") (pinfunction "6_3") (pintype "input"))
      (node (ref "R24") (pin "1") (pinfunction "1_1") (pintype "passive"))
      (node (ref "U$12") (pin "G") (pinfunction "7_G") (pintype "passive"))
    )
    (net (code "35") (name "Net-(IC3A-7)") (class "Default")
      (node (ref "IC3") (pin "4") (pinfunction "7_4") (pintype "input"))
      (node (ref "R25") (pin "1") (pinfunction "1_1") (pintype "passive"))
      (node (ref "U$12") (pin "H") (pinfunction "8_H") (pintype "passive"))
    )
    (net (code "36") (name "Net-(OK1-A)") (class "Default")
      (node (ref "D1") (pin "C") (pinfunction "C_C") (pintype "passive"))
      (node (ref "OK1") (pin "2") (pinfunction "A_2") (pintype "passive"))
      (node (ref "R11") (pin "2") (pinfunction "2_2") (pintype "passive"))
    )
    (net (code "37") (name "Net-(OK1-C)") (class "Default")
      (node (ref "D1") (pin "A") (pinfunction "A_A") (pintype "passive"))
      (node (ref "OK1") (pin "3") (pinfunction "C_3") (pintype "passive"))
      (node (ref "X1") (pin "5") (pinfunction "5_5") (pintype "passive"))
    )
    (net (code "38") (name "Net-(OK1-VB)") (class "Default")
      (node (ref "OK1") (pin "7") (pinfunction "VB_7") (pintype "passive"))
      (node (ref "R17") (pin "2") (pinfunction "2_2") (pintype "passive"))
    )
    (net (code "39") (name "Net-(R3-Pad1)") (class "Default")
      (node (ref "R3") (pin "1") (pinfunction "1_1") (pintype "passive"))
      (node (ref "T1") (pin "B") (pinfunction "B_B") (pintype "passive"))
    )
    (net (code "40") (name "Net-(R4-Pad1)") (class "Default")
      (node (ref "R4") (pin "1") (pinfunction "1_1") (pintype "passive"))
      (node (ref "T2") (pin "B") (pinfunction "B_B") (pintype "passive"))
    )
    (net (code "41") (name "Net-(R6-Pad1)") (class "Default")
      (node (ref "R6") (pin "1") (pinfunction "1_1") (pintype "passive"))
      (node (ref "T3") (pin "B") (pinfunction "B_B") (pintype "passive"))
    )
    (net (code "42") (name "Net-(R9-Pad1)") (class "Default")
      (node (ref "R9") (pin "1") (pinfunction "1_1") (pintype "passive"))
      (node (ref "T4") (pin "B") (pinfunction "B_B") (pintype "passive"))
    )
    (net (code "43") (name "Net-(R11-Pad1)") (class "Default")
      (node (ref "R11") (pin "1") (pinfunction "1_1") (pintype "passive"))
      (node (ref "X1") (pin "4") (pinfunction "4_4") (pintype "passive"))
    )
    (net (code "44") (name "Net-(U$9-O)") (class "Default")
      (node (ref "R14") (pin "2") (pinfunction "2_2") (pintype "passive"))
      (node (ref "U$9") (pin "1") (pinfunction "O_1") (pintype "passive"))
    )
    (net (code "45") (name "Net-(U$10-O)") (class "Default")
      (node (ref "R16") (pin "2") (pinfunction "2_2") (pintype "passive"))
      (node (ref "U$10") (pin "1") (pinfunction "O_1") (pintype "passive"))
    )
    (net (code "46") (name "Net-(U1-~{CLR})") (class "Default")
      (node (ref "R2") (pin "1") (pinfunction "1_1") (pintype "passive"))
      (node (ref "U1") (pin "11") (pinfunction "~{CLR}_11") (pintype "input"))
    )
    (net (code "47") (name "Net-(U3-PB6(XTAL1{slash}TOSC1))") (class "Default")
      (node (ref "C1") (pin "2") (pinfunction "2_2") (pintype "passive"))
      (node (ref "Q1") (pin "2") (pinfunction "2_2") (pintype "passive"))
      (node (ref "U3") (pin "7") (pinfunction "PB6(XTAL1/TOSC1)_7") (pintype "bidirectional"))
    )
    (net (code "48") (name "Net-(U3-PB7(XTAL2{slash}TOSC2))") (class "Default")
      (node (ref "C2") (pin "2") (pinfunction "2_2") (pintype "passive"))
      (node (ref "Q1") (pin "1") (pinfunction "1_1") (pintype "passive"))
      (node (ref "U3") (pin "8") (pinfunction "PB7(XTAL2/TOSC2)_8") (pintype "bidirectional"))
    )
    (net (code "49") (name "Net-(U3-PD0(RXD))") (class "Default")
      (node (ref "JP1") (pin "1") (pinfunction "1_1") (pintype "passive"))
      (node (ref "U3") (pin "30") (pinfunction "PD0(RXD)_30") (pintype "bidirectional"))
    )
    (net (code "50") (name "Net-(U4-D+)") (class "Default")
      (node (ref "R27") (pin "2") (pinfunction "2_2") (pintype "passive"))
      (node (ref "U4") (pin "21") (pinfunction "D+_21") (pintype "bidirectional"))
    )
    (net (code "51") (name "Net-(U4-D-)") (class "Default")
      (node (ref "R26") (pin "2") (pinfunction "2_2") (pintype "passive"))
      (node (ref "U4") (pin "20") (pinfunction "D-_20") (pintype "bidirectional"))
    )
    (net (code "52") (name "Net-(U4-X0)") (class "Default")
      (node (ref "C8") (pin "2") (pinfunction "2_2") (pintype "passive"))
      (node (ref "Q2") (pin "2") (pinfunction "2_2") (pintype "passive"))
      (node (ref "U4") (pin "25") (pinfunction "X0_25") (pintype "bidirectional"))
    )
    (net (code "53") (name "Net-(U4-X1)") (class "Default")
      (node (ref "C7") (pin "2") (pinfunction "2_2") (pintype "passive"))
      (node (ref "Q2") (pin "1") (pinfunction "1_1") (pintype "passive"))
      (node (ref "U4") (pin "24") (pinfunction "X1_24") (pintype "bidirectional"))
    )
    (net (code "54") (name "ROTARY_D0") (class "Default")
      (node (ref "IC3") (pin "9") (pinfunction "A0_9") (pintype "output"))
      (node (ref "U3") (pin "32") (pinfunction "PD2(INT0)_32") (pintype "bidirectional"))
    )
    (net (code "55") (name "ROTARY_D1") (class "Default")
      (node (ref "IC3") (pin "7") (pinfunction "A1_7") (pintype "output"))
      (node (ref "U3") (pin "1") (pinfunction "PD3(INT1)_1") (pintype "bidirectional"))
    )
    (net (code "56") (name "ROTARY_D2") (class "Default")
      (node (ref "IC3") (pin "6") (pinfunction "A2_6") (pintype "output"))
      (node (ref "U3") (pin "2") (pinfunction "PD4(XCK/T0)_2") (pintype "bidirectional"))
    )
    (net (code "57") (name "RST") (class "Default")
      (node (ref "ISP1") (pin "5") (pinfunction "RST_5") (pintype "output"))
      (node (ref "U3") (pin "29") (pinfunction "PC6(/RESET)_29") (pintype "bidirectional"))
    )
    (net (code "58") (name "RST_USB") (class "Default")
      (node (ref "IC1") (pin "12") (pinfunction "I_12") (pintype "input"))
      (node (ref "U3") (pin "11") (pinfunction "PD7(AIN1)_11") (pintype "bidirectional"))
    )
    (net (code "59") (name "RST_USB_3V3") (class "Default")
      (node (ref "IC1") (pin "11") (pinfunction "O_11") (pintype "tri_state"))
      (node (ref "U4") (pin "12") (pinfunction "RES_12") (pintype "bidirectional"))
    )
    (net (code "60") (name "SCK") (class "Default")
      (node (ref "IC1") (pin "2") (pinfunction "I_2") (pintype "input"))
      (node (ref "ISP1") (pin "3") (pinfunction "SCK_3") (pintype "output"))
      (node (ref "U1") (pin "8") (pinfunction "SCLK_8") (pintype "input"))
      (node (ref "U3") (pin "17") (pinfunction "PB5(SCK)_17") (pintype "bidirectional"))
    )
    (net (code "61") (name "SCK_3V3") (class "Default")
      (node (ref "IC1") (pin "3") (pinfunction "O_3") (pintype "tri_state"))
      (node (ref "U4") (pin "13") (pinfunction "SCK_13") (pintype "bidirectional"))
    )
    (net (code "62") (name "SPEED_VAL") (class "Default")
      (node (ref "U$11") (pin "P$2") (pinfunction "2_P$2") (pintype "passive"))
      (node (ref "U3") (pin "27") (pinfunction "PC4(ADC4/SDA)_27") (pintype "bidirectional"))
    )
    (net (code "63") (name "SS_DAC") (class "Default")
      (node (ref "U1") (pin "7") (pinfunction "~{SYNC}_7") (pintype "input"))
      (node (ref "U3") (pin "14") (pinfunction "PB2(SS/OC1B)_14") (pintype "bidirectional"))
    )
    (net (code "64") (name "SS_USB") (class "Default")
      (node (ref "IC1") (pin "5") (pinfunction "I_5") (pintype "input"))
      (node (ref "IC4") (pin "1") (pinfunction "OE_1") (pintype "input"))
      (node (ref "U3") (pin "12") (pinfunction "PB0(ICP)_12") (pintype "bidirectional"))
    )
    (net (code "65") (name "SS_USB_3V3") (class "Default")
      (node (ref "IC1") (pin "6") (pinfunction "O_6") (pintype "tri_state"))
      (node (ref "U4") (pin "14") (pinfunction "SS_14") (pintype "bidirectional"))
    )
    (net (code "66") (name "SWITCH0_VAL") (class "Default")
      (node (ref "R13") (pin "1") (pinfunction "1_1") (pintype "passive"))
      (node (ref "U$9") (pin "2") (pinfunction "P_2") (pintype "passive"))
      (node (ref "U3") (pin "19") (pinfunction "ADC6_19") (pintype "bidirectional"))
    )
    (net (code "67") (name "SWITCH1_VAL") (class "Default")
      (node (ref "R15") (pin "1") (pinfunction "1_1") (pintype "passive"))
      (node (ref "U$10") (pin "2") (pinfunction "P_2") (pintype "passive"))
      (node (ref "U3") (pin "22") (pinfunction "ADC7_22") (pintype "bidirectional"))
    )
    (net (code "68") (name "USB_D_N") (class "Default")
      (node (ref "R26") (pin "1") (pinfunction "1_1") (pintype "passive"))
      (node (ref "X2") (pin "2") (pinfunction "2_2") (pintype "passive"))
    )
    (net (code "69") (name "USB_D_P") (class "Default")
      (node (ref "R27") (pin "1") (pinfunction "1_1") (pintype "passive"))
      (node (ref "X2") (pin "3") (pinfunction "3_3") (pintype "passive"))
    )
    (net (code "70") (name "unconnected-(IC3A-EO-Pad15)") (class "Default")
      (node (ref "IC3") (pin "15") (pinfunction "EO_15") (pintype "output"))
    )
    (net (code "71") (name "unconnected-(IC3A-GS-Pad14)") (class "Default")
      (node (ref "IC3") (pin "14") (pinfunction "GS_14") (pintype "output"))
    )
    (net (code "72") (name "unconnected-(U$1-3-PadP$2)") (class "Default")
      (node (ref "U$1") (pin "P$2") (pinfunction "3_P$2") (pintype "passive"))
    )
    (net (code "73") (name "unconnected-(U$2-3-PadP$2)") (class "Default")
      (node (ref "U$2") (pin "P$2") (pinfunction "3_P$2") (pintype "passive"))
    )
    (net (code "74") (name "unconnected-(U$3-3-PadP$2)") (class "Default")
      (node (ref "U$3") (pin "P$2") (pinfunction "3_P$2") (pintype "passive"))
    )
    (net (code "75") (name "unconnected-(U$4-3-PadP$2)") (class "Default")
      (node (ref "U$4") (pin "P$2") (pinfunction "3_P$2") (pintype "passive"))
    )
    (net (code "76") (name "unconnected-(U$5-3-PadP$2)") (class "Default")
      (node (ref "U$5") (pin "P$2") (pinfunction "3_P$2") (pintype "passive"))
    )
    (net (code "77") (name "unconnected-(U$6-3-PadP$2)") (class "Default")
      (node (ref "U$6") (pin "P$2") (pinfunction "3_P$2") (pintype "passive"))
    )
    (net (code "78") (name "unconnected-(U$7-3-PadP$2)") (class "Default")
      (node (ref "U$7") (pin "P$2") (pinfunction "3_P$2") (pintype "passive"))
    )
    (net (code "79") (name "unconnected-(U$8-3-PadP$2)") (class "Default")
      (node (ref "U$8") (pin "P$2") (pinfunction "3_P$2") (pintype "passive"))
    )
    (net (code "80") (name "unconnected-(U1-1_NC-Pad2)") (class "Default")
      (node (ref "U1") (pin "2") (pinfunction "1_NC_2") (pintype "passive"))
    )
    (net (code "81") (name "unconnected-(U1-2_NC-Pad6)") (class "Default")
      (node (ref "U1") (pin "6") (pinfunction "2_NC_6") (pintype "passive"))
    )
    (net (code "82") (name "unconnected-(U1-3_NC-Pad12)") (class "Default")
      (node (ref "U1") (pin "12") (pinfunction "3_NC_12") (pintype "passive"))
    )
    (net (code "83") (name "unconnected-(U1-4_NC-Pad13)") (class "Default")
      (node (ref "U1") (pin "13") (pinfunction "4_NC_13") (pintype "passive"))
    )
    (net (code "84") (name "unconnected-(U1-SDO-Pad16)") (class "Default")
      (node (ref "U1") (pin "16") (pinfunction "SDO_16") (pintype "output"))
    )
    (net (code "85") (name "unconnected-(U2-NC-Pad3)") (class "Default")
      (node (ref "U2") (pin "3") (pinfunction "NC_3") (pintype "passive"))
    )
    (net (code "86") (name "unconnected-(U3-AREF-Pad20)") (class "Default")
      (node (ref "U3") (pin "20") (pinfunction "AREF_20") (pintype "bidirectional"))
    )
    (net (code "87") (name "unconnected-(U3-PC0(ADC0)-Pad23)") (class "Default")
      (node (ref "U3") (pin "23") (pinfunction "PC0(ADC0)_23") (pintype "bidirectional"))
    )
    (net (code "88") (name "unconnected-(U3-PD1(TXD)-Pad31)") (class "Default")
      (node (ref "U3") (pin "31") (pinfunction "PD1(TXD)_31") (pintype "bidirectional"))
    )
    (net (code "89") (name "unconnected-(U3-PD5(T1)-Pad9)") (class "Default")
      (node (ref "U3") (pin "9") (pinfunction "PD5(T1)_9") (pintype "bidirectional"))
    )
    (net (code "90") (name "unconnected-(U3-PD6(AIN0)-Pad10)") (class "Default")
      (node (ref "U3") (pin "10") (pinfunction "PD6(AIN0)_10") (pintype "bidirectional"))
    )
    (net (code "91") (name "unconnected-(U4-GOUT0-Pad4)") (class "Default")
      (node (ref "U4") (pin "4") (pinfunction "GOUT0_4") (pintype "bidirectional"))
    )
    (net (code "92") (name "unconnected-(U4-GOUT1-Pad5)") (class "Default")
      (node (ref "U4") (pin "5") (pinfunction "GOUT1_5") (pintype "bidirectional"))
    )
    (net (code "93") (name "unconnected-(U4-GOUT2-Pad6)") (class "Default")
      (node (ref "U4") (pin "6") (pinfunction "GOUT2_6") (pintype "bidirectional"))
    )
    (net (code "94") (name "unconnected-(U4-GOUT3-Pad7)") (class "Default")
      (node (ref "U4") (pin "7") (pinfunction "GOUT3_7") (pintype "bidirectional"))
    )
    (net (code "95") (name "unconnected-(U4-GOUT4-Pad8)") (class "Default")
      (node (ref "U4") (pin "8") (pinfunction "GOUT4_8") (pintype "bidirectional"))
    )
    (net (code "96") (name "unconnected-(U4-GOUT5-Pad9)") (class "Default")
      (node (ref "U4") (pin "9") (pinfunction "GOUT5_9") (pintype "bidirectional"))
    )
    (net (code "97") (name "unconnected-(U4-GOUT6-Pad10)") (class "Default")
      (node (ref "U4") (pin "10") (pinfunction "GOUT6_10") (pintype "bidirectional"))
    )
    (net (code "98") (name "unconnected-(U4-GOUT7-Pad11)") (class "Default")
      (node (ref "U4") (pin "11") (pinfunction "GOUT7_11") (pintype "bidirectional"))
    )
    (net (code "99") (name "unconnected-(U4-GPIN0-Pad26)") (class "Default")
      (node (ref "U4") (pin "26") (pinfunction "GPIN0_26") (pintype "bidirectional"))
    )
    (net (code "100") (name "unconnected-(U4-GPIN1-Pad27)") (class "Default")
      (node (ref "U4") (pin "27") (pinfunction "GPIN1_27") (pintype "bidirectional"))
    )
    (net (code "101") (name "unconnected-(U4-GPIN2-Pad28)") (class "Default")
      (node (ref "U4") (pin "28") (pinfunction "GPIN2_28") (pintype "bidirectional"))
    )
    (net (code "102") (name "unconnected-(U4-GPIN3-Pad29)") (class "Default")
      (node (ref "U4") (pin "29") (pinfunction "GPIN3_29") (pintype "bidirectional"))
    )
    (net (code "103") (name "unconnected-(U4-GPIN4-Pad30)") (class "Default")
      (node (ref "U4") (pin "30") (pinfunction "GPIN4_30") (pintype "bidirectional"))
    )
    (net (code "104") (name "unconnected-(U4-GPIN5-Pad31)") (class "Default")
      (node (ref "U4") (pin "31") (pinfunction "GPIN5_31") (pintype "bidirectional"))
    )
    (net (code "105") (name "unconnected-(U4-GPIN6-Pad32)") (class "Default")
      (node (ref "U4") (pin "32") (pinfunction "GPIN6_32") (pintype "bidirectional"))
    )
    (net (code "106") (name "unconnected-(U4-GPIN7-Pad1)") (class "Default")
      (node (ref "U4") (pin "1") (pinfunction "GPIN7_1") (pintype "bidirectional"))
    )
    (net (code "107") (name "unconnected-(U4-GPX-Pad17)") (class "Default")
      (node (ref "U4") (pin "17") (pinfunction "GPX_17") (pintype "bidirectional"))
    )
    (net (code "108") (name "unconnected-(U4-VBCOMP-Pad22)") (class "Default")
      (node (ref "U4") (pin "22") (pinfunction "VBCOMP_22") (pintype "bidirectional"))
    )
    (net (code "109") (name "unconnected-(X1-Pad1)") (class "Default")
      (node (ref "X1") (pin "1") (pinfunction "1_1") (pintype "passive"))
    )
    (net (code "110") (name "unconnected-(X1-Pad2)") (class "Default")
      (node (ref "X1") (pin "2") (pinfunction "2_2") (pintype "passive"))
    )
    (net (code "111") (name "unconnected-(X1-Pad3)") (class "Default")
      (node (ref "X1") (pin "3") (pinfunction "3_3") (pintype "passive"))
    )
  )
)
